# KGBuffer.net
KiCad netlist of a schematic drawn in EAGLE
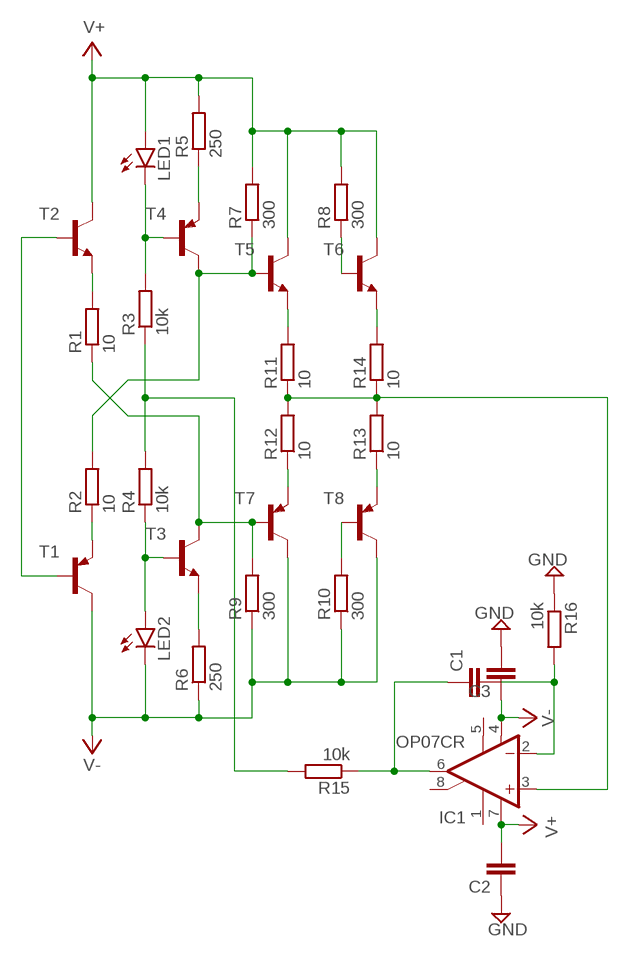
[diagram p0: schematic, sheet 1]

(export (version "E")
  (design (tool "Eeschema 10.0.6"))
  (components
    (comp (ref "C1")
      (value "C-EUC0603K")
      (footprint "eagle-import:C0603K")
      (libsource (lib "eagle-import") (part "C-EUC0603K"))
    )
    (comp (ref "C2")
      (value "C-EUC0805K")
      (footprint "eagle-import:C0805K")
      (libsource (lib "eagle-import") (part "C-EUC0805K"))
    )
    (comp (ref "C3")
      (value "C-EUC0805K")
      (footprint "eagle-import:C0805K")
      (libsource (lib "eagle-import") (part "C-EUC0805K"))
    )
    (comp (ref "IC1")
      (value "OP07CR")
      (footprint "eagle-import:SO08")
      (libsource (lib "eagle-import") (part "OP07RC"))
    )
    (comp (ref "LED1")
      (value "LEDSMT1206")
      (footprint "eagle-import:1206")
      (libsource (lib "eagle-import") (part "LEDSMT1206"))
    )
    (comp (ref "LED2")
      (value "LEDSMT1206")
      (footprint "eagle-import:1206")
      (libsource (lib "eagle-import") (part "LEDSMT1206"))
    )
    (comp (ref "R1")
      (value "10")
      (footprint "eagle-import:MINI_MELF-0204W")
      (libsource (lib "eagle-import") (part "R-EU_MELF0204W"))
    )
    (comp (ref "R2")
      (value "10")
      (footprint "eagle-import:MINI_MELF-0204W")
      (libsource (lib "eagle-import") (part "R-EU_MELF0204W"))
    )
    (comp (ref "R3")
      (value "10k")
      (footprint "eagle-import:MINI_MELF-0204W")
      (libsource (lib "eagle-import") (part "R-EU_MELF0204W"))
    )
    (comp (ref "R4")
      (value "10k")
      (footprint "eagle-import:MINI_MELF-0204W")
      (libsource (lib "eagle-import") (part "R-EU_MELF0204W"))
    )
    (comp (ref "R5")
      (value "250")
      (footprint "eagle-import:MINI_MELF-0204W")
      (libsource (lib "eagle-import") (part "R-EU_MELF0204W"))
    )
    (comp (ref "R6")
      (value "250")
      (footprint "eagle-import:MINI_MELF-0204W")
      (libsource (lib "eagle-import") (part "R-EU_MELF0204W"))
    )
    (comp (ref "R7")
      (value "300")
      (footprint "eagle-import:MINI_MELF-0204W")
      (libsource (lib "eagle-import") (part "R-EU_MELF0204W"))
    )
    (comp (ref "R8")
      (value "300")
      (footprint "eagle-import:MINI_MELF-0204W")
      (libsource (lib "eagle-import") (part "R-EU_MELF0204W"))
    )
    (comp (ref "R9")
      (value "300")
      (footprint "eagle-import:MINI_MELF-0204W")
      (libsource (lib "eagle-import") (part "R-EU_MELF0204W"))
    )
    (comp (ref "R10")
      (value "300")
      (footprint "eagle-import:MINI_MELF-0204W")
      (libsource (lib "eagle-import") (part "R-EU_MELF0204W"))
    )
    (comp (ref "R11")
      (value "10")
      (footprint "eagle-import:MINI_MELF-0204W")
      (libsource (lib "eagle-import") (part "R-EU_MELF0204W"))
    )
    (comp (ref "R12")
      (value "10")
      (footprint "eagle-import:MINI_MELF-0204W")
      (libsource (lib "eagle-import") (part "R-EU_MELF0204W"))
    )
    (comp (ref "R13")
      (value "10")
      (footprint "eagle-import:MINI_MELF-0204W")
      (libsource (lib "eagle-import") (part "R-EU_MELF0204W"))
    )
    (comp (ref "R14")
      (value "10")
      (footprint "eagle-import:MINI_MELF-0204W")
      (libsource (lib "eagle-import") (part "R-EU_MELF0204W"))
    )
    (comp (ref "R15")
      (value "10k")
      (footprint "eagle-import:MINI_MELF-0204W")
      (libsource (lib "eagle-import") (part "R-EU_MELF0204W"))
    )
    (comp (ref "R16")
      (value "10k")
      (footprint "eagle-import:MINI_MELF-0204W")
      (libsource (lib "eagle-import") (part "R-EU_MELF0204W"))
    )
    (comp (ref "T1")
      (value "BC856BLT1-PNP-SOT23-BEC")
      (footprint "eagle-import:SOT23-BEC")
      (libsource (lib "eagle-import") (part "-PNP-SOT23-BECBC856BLT1"))
    )
    (comp (ref "T2")
      (value "BC846-NPN-SOT23-BEC")
      (footprint "eagle-import:SOT23-BEC")
      (libsource (lib "eagle-import") (part "-NPN-SOT23-BECBC846"))
    )
    (comp (ref "T3")
      (value "BC846-NPN-SOT23-BEC")
      (footprint "eagle-import:SOT23-BEC")
      (libsource (lib "eagle-import") (part "-NPN-SOT23-BECBC846"))
    )
    (comp (ref "T4")
      (value "BC856BLT1-PNP-SOT23-BEC")
      (footprint "eagle-import:SOT23-BEC")
      (libsource (lib "eagle-import") (part "-PNP-SOT23-BECBC856BLT1"))
    )
    (comp (ref "T5")
      (value "BC846-NPN-SOT23-BEC")
      (footprint "eagle-import:SOT23-BEC")
      (libsource (lib "eagle-import") (part "-NPN-SOT23-BECBC846"))
    )
    (comp (ref "T6")
      (value "BC846-NPN-SOT23-BEC")
      (footprint "eagle-import:SOT23-BEC")
      (libsource (lib "eagle-import") (part "-NPN-SOT23-BECBC846"))
    )
    (comp (ref "T7")
      (value "BC856BLT1-PNP-SOT23-BEC")
      (footprint "eagle-import:SOT23-BEC")
      (libsource (lib "eagle-import") (part "-PNP-SOT23-BECBC856BLT1"))
    )
    (comp (ref "T8")
      (value "BC856BLT1-PNP-SOT23-BEC")
      (footprint "eagle-import:SOT23-BEC")
      (libsource (lib "eagle-import") (part "-PNP-SOT23-BECBC856BLT1"))
    )
  )
  (nets
    (net (code "1") (name "GND") (class "Default")
      (node (ref "C2") (pin "1") (pinfunction "1_1") (pintype "passive"))
      (node (ref "C3") (pin "2") (pinfunction "2_2") (pintype "passive"))
      (node (ref "R16") (pin "1") (pinfunction "1_1") (pintype "passive"))
    )
    (net (code "2") (name "Net-(IC1-+IN)") (class "Default")
      (node (ref "IC1") (pin "3") (pinfunction "+IN_3") (pintype "input"))
      (node (ref "R11") (pin "1") (pinfunction "1_1") (pintype "passive"))
      (node (ref "R12") (pin "2") (pinfunction "2_2") (pintype "passive"))
      (node (ref "R13") (pin "2") (pinfunction "2_2") (pintype "passive"))
      (node (ref "R14") (pin "1") (pinfunction "1_1") (pintype "passive"))
    )
    (net (code "3") (name "Net-(IC1--IN)") (class "Default")
      (node (ref "C1") (pin "2") (pinfunction "2_2") (pintype "passive"))
      (node (ref "IC1") (pin "2") (pinfunction "-IN_2") (pintype "input"))
      (node (ref "R16") (pin "2") (pinfunction "2_2") (pintype "passive"))
    )
    (net (code "4") (name "Net-(IC1-OUT)") (class "Default")
      (node (ref "C1") (pin "1") (pinfunction "1_1") (pintype "passive"))
      (node (ref "IC1") (pin "6") (pinfunction "OUT_6") (pintype "output"))
      (node (ref "R15") (pin "1") (pinfunction "1_1") (pintype "passive"))
    )
    (net (code "5") (name "Net-(LED1-PadC)") (class "Default")
      (node (ref "LED1") (pin "C") (pinfunction "C_C") (pintype "passive"))
      (node (ref "R3") (pin "2") (pinfunction "2_2") (pintype "passive"))
      (node (ref "T4") (pin "B") (pinfunction "B_B") (pintype "passive"))
    )
    (net (code "6") (name "Net-(LED2-PadA)") (class "Default")
      (node (ref "LED2") (pin "A") (pinfunction "A_A") (pintype "passive"))
      (node (ref "R4") (pin "1") (pinfunction "1_1") (pintype "passive"))
      (node (ref "T3") (pin "B") (pinfunction "B_B") (pintype "passive"))
    )
    (net (code "7") (name "Net-(R1-Pad1)") (class "Default")
      (node (ref "R1") (pin "1") (pinfunction "1_1") (pintype "passive"))
      (node (ref "R9") (pin "2") (pinfunction "2_2") (pintype "passive"))
      (node (ref "T3") (pin "C") (pinfunction "C_C") (pintype "passive"))
      (node (ref "T7") (pin "B") (pinfunction "B_B") (pintype "passive"))
    )
    (net (code "8") (name "Net-(R1-Pad2)") (class "Default")
      (node (ref "R1") (pin "2") (pinfunction "2_2") (pintype "passive"))
      (node (ref "T2") (pin "E") (pinfunction "E_E") (pintype "passive"))
    )
    (net (code "9") (name "Net-(R2-Pad1)") (class "Default")
      (node (ref "R2") (pin "1") (pinfunction "1_1") (pintype "passive"))
      (node (ref "T1") (pin "E") (pinfunction "E_E") (pintype "passive"))
    )
    (net (code "10") (name "Net-(R2-Pad2)") (class "Default")
      (node (ref "R2") (pin "2") (pinfunction "2_2") (pintype "passive"))
      (node (ref "R7") (pin "1") (pinfunction "1_1") (pintype "passive"))
      (node (ref "T4") (pin "C") (pinfunction "C_C") (pintype "passive"))
      (node (ref "T5") (pin "B") (pinfunction "B_B") (pintype "passive"))
    )
    (net (code "11") (name "Net-(R5-Pad1)") (class "Default")
      (node (ref "R5") (pin "1") (pinfunction "1_1") (pintype "passive"))
      (node (ref "T4") (pin "E") (pinfunction "E_E") (pintype "passive"))
    )
    (net (code "12") (name "Net-(R6-Pad2)") (class "Default")
      (node (ref "R6") (pin "2") (pinfunction "2_2") (pintype "passive"))
      (node (ref "T3") (pin "E") (pinfunction "E_E") (pintype "passive"))
    )
    (net (code "13") (name "Net-(R8-Pad1)") (class "Default")
      (node (ref "R8") (pin "1") (pinfunction "1_1") (pintype "passive"))
      (node (ref "T6") (pin "B") (pinfunction "B_B") (pintype "passive"))
    )
    (net (code "14") (name "Net-(R10-Pad2)") (class "Default")
      (node (ref "R10") (pin "2") (pinfunction "2_2") (pintype "passive"))
      (node (ref "T8") (pin "B") (pinfunction "B_B") (pintype "passive"))
    )
    (net (code "15") (name "Net-(R11-Pad2)") (class "Default")
      (node (ref "R11") (pin "2") (pinfunction "2_2") (pintype "passive"))
      (node (ref "T5") (pin "E") (pinfunction "E_E") (pintype "passive"))
    )
    (net (code "16") (name "Net-(R12-Pad1)") (class "Default")
      (node (ref "R12") (pin "1") (pinfunction "1_1") (pintype "passive"))
      (node (ref "T7") (pin "E") (pinfunction "E_E") (pintype "passive"))
    )
    (net (code "17") (name "Net-(R13-Pad1)") (class "Default")
      (node (ref "R13") (pin "1") (pinfunction "1_1") (pintype "passive"))
      (node (ref "T8") (pin "E") (pinfunction "E_E") (pintype "passive"))
    )
    (net (code "18") (name "Net-(R14-Pad2)") (class "Default")
      (node (ref "R14") (pin "2") (pinfunction "2_2") (pintype "passive"))
      (node (ref "T6") (pin "E") (pinfunction "E_E") (pintype "passive"))
    )
    (net (code "19") (name "Net-(R15-Pad2)") (class "Default")
      (node (ref "R15") (pin "2") (pinfunction "2_2") (pintype "passive"))
      (node (ref "R3") (pin "1") (pinfunction "1_1") (pintype "passive"))
      (node (ref "R4") (pin "2") (pinfunction "2_2") (pintype "passive"))
    )
    (net (code "20") (name "Net-(T1-PadB)") (class "Default")
      (node (ref "T1") (pin "B") (pinfunction "B_B") (pintype "passive"))
      (node (ref "T2") (pin "B") (pinfunction "B_B") (pintype "passive"))
    )
    (net (code "21") (name "V+") (class "Default")
      (node (ref "C2") (pin "2") (pinfunction "2_2") (pintype "passive"))
      (node (ref "IC1") (pin "7") (pinfunction "V+_7") (pintype "power_in"))
      (node (ref "LED1") (pin "A") (pinfunction "A_A") (pintype "passive"))
      (node (ref "R5") (pin "2") (pinfunction "2_2") (pintype "passive"))
      (node (ref "R7") (pin "2") (pinfunction "2_2") (pintype "passive"))
      (node (ref "R8") (pin "2") (pinfunction "2_2") (pintype "passive"))
      (node (ref "T2") (pin "C") (pinfunction "C_C") (pintype "passive"))
      (node (ref "T5") (pin "C") (pinfunction "C_C") (pintype "passive"))
      (node (ref "T6") (pin "C") (pinfunction "C_C") (pintype "passive"))
    )
    (net (code "22") (name "V-") (class "Default")
      (node (ref "C3") (pin "1") (pinfunction "1_1") (pintype "passive"))
      (node (ref "IC1") (pin "4") (pinfunction "V-_4") (pintype "power_in"))
      (node (ref "LED2") (pin "C") (pinfunction "C_C") (pintype "passive"))
      (node (ref "R10") (pin "1") (pinfunction "1_1") (pintype "passive"))
      (node (ref "R6") (pin "1") (pinfunction "1_1") (pintype "passive"))
      (node (ref "R9") (pin "1") (pinfunction "1_1") (pintype "passive"))
      (node (ref "T1") (pin "C") (pinfunction "C_C") (pintype "passive"))
      (node (ref "T7") (pin "C") (pinfunction "C_C") (pintype "passive"))
      (node (ref "T8") (pin "C") (pinfunction "C_C") (pintype "passive"))
    )
    (net (code "23") (name "unconnected-(IC1-ON1-Pad1)") (class "Default")
      (node (ref "IC1") (pin "1") (pinfunction "ON1_1") (pintype "passive"))
    )
    (net (code "24") (name "unconnected-(IC1-ON2-Pad8)") (class "Default")
      (node (ref "IC1") (pin "8") (pinfunction "ON2_8") (pintype "passive"))
    )
    (net (code "25") (name "unconnected-(IC1-OPT-Pad5)") (class "Default")
      (node (ref "IC1") (pin "5") (pinfunction "OPT_5") (pintype "passive"))
    )
  )
)
